# cpuinterface.net
KiCad netlist of a schematic drawn in Altium Designer
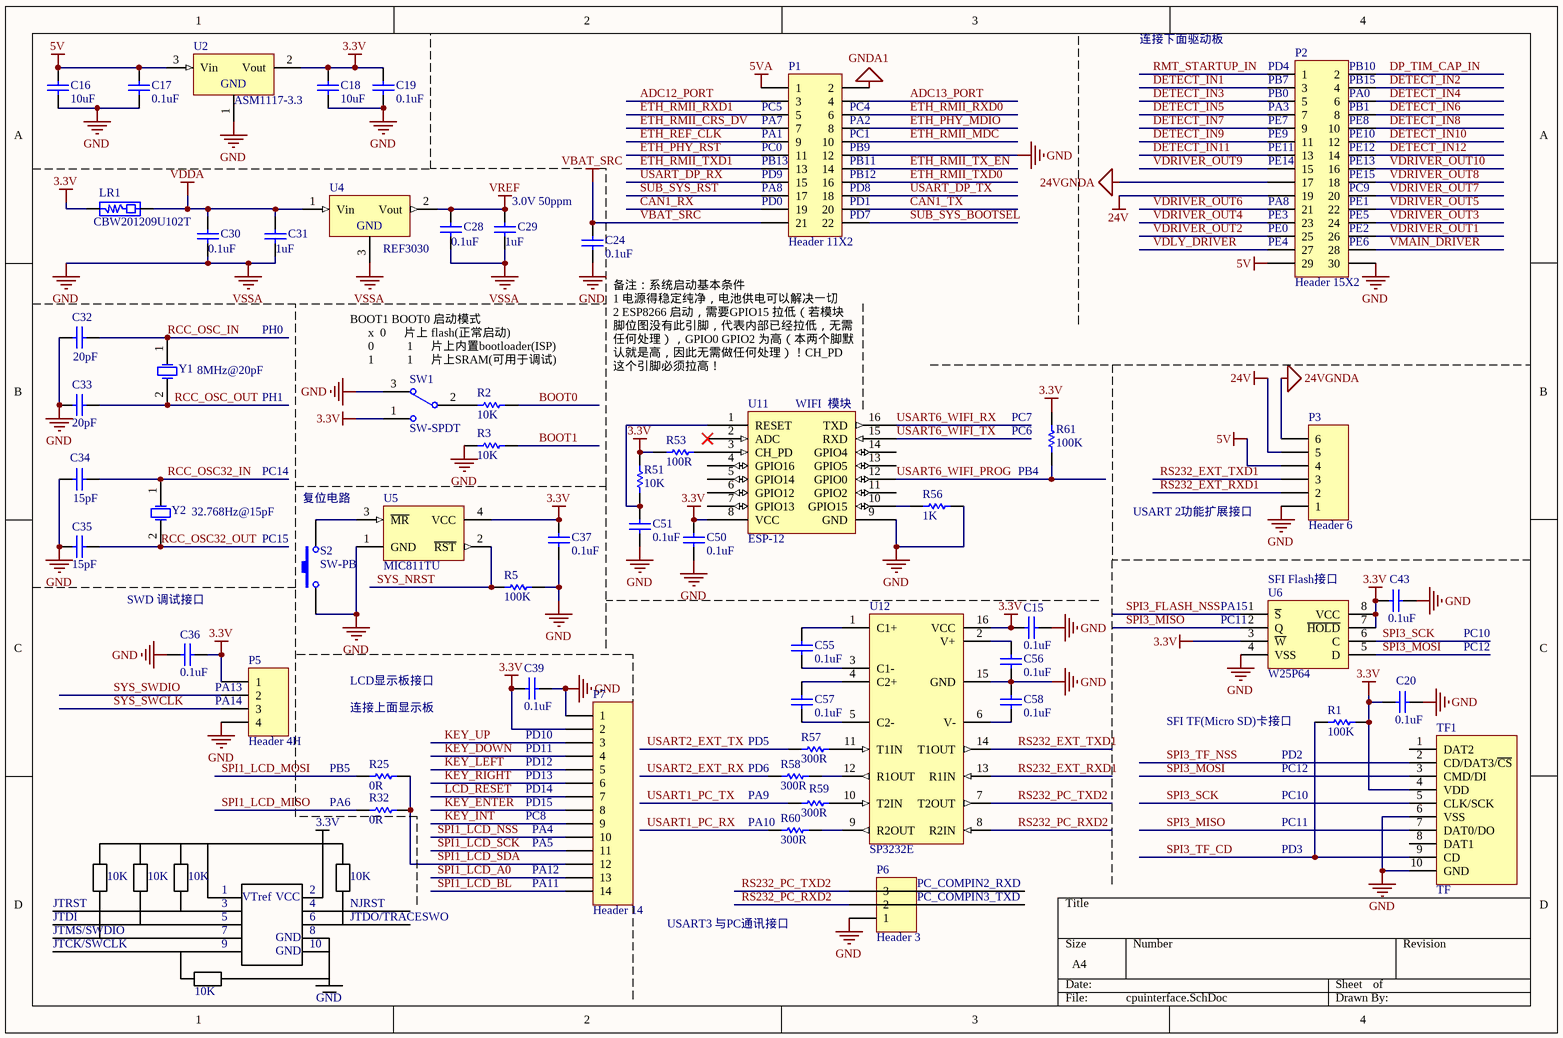
[diagram p0: cpuinterface.SchDoc]

(export (version "E")
  (design (tool "Eeschema 10.0.6"))
  (components
    (comp (ref "C15")
      (value "0.1uF")
      (footprint "CAPC2012M")
      (description "Capacitor")
      (fields (field (name "PUBLISHER") "Altium Limited"))
      (libsource (lib "Miscellaneous Devices") (part "Cap"))
    )
    (comp (ref "C16")
      (value "10uF")
      (footprint "CAPC2012M")
      (description "Capacitor")
      (fields (field (name "PUBLISHER") "Altium Limited"))
      (libsource (lib "Miscellaneous Devices") (part "Cap"))
    )
    (comp (ref "C17")
      (value "0.1uF")
      (footprint "CAPC2012M")
      (description "Capacitor")
      (fields (field (name "PUBLISHER") "Altium Limited"))
      (libsource (lib "Miscellaneous Devices") (part "Cap"))
    )
    (comp (ref "C18")
      (value "10uF")
      (footprint "CAPC2012M")
      (description "Capacitor")
      (fields (field (name "PUBLISHER") "Altium Limited"))
      (libsource (lib "Miscellaneous Devices") (part "Cap"))
    )
    (comp (ref "C19")
      (value "0.1uF")
      (footprint "CAPC2012M")
      (description "Capacitor")
      (fields (field (name "PUBLISHER") "Altium Limited"))
      (libsource (lib "Miscellaneous Devices") (part "Cap"))
    )
    (comp (ref "C20")
      (value "0.1uF")
      (footprint "CAPC2012M")
      (description "Capacitor")
      (fields (field (name "PUBLISHER") "Altium Limited"))
      (libsource (lib "Miscellaneous Devices") (part "Cap"))
    )
    (comp (ref "C24")
      (value "0.1uF")
      (footprint "CAPC2012M")
      (description "Capacitor")
      (fields (field (name "PUBLISHER") "Altium Limited"))
      (libsource (lib "Miscellaneous Devices") (part "Cap"))
    )
    (comp (ref "C28")
      (value "0.1uF")
      (footprint "CAPC2012M")
      (description "Capacitor")
      (fields (field (name "PUBLISHER") "Altium Limited"))
      (libsource (lib "Miscellaneous Devices") (part "Cap"))
    )
    (comp (ref "C29")
      (value "1uF")
      (footprint "CAPC2012M")
      (description "Capacitor")
      (fields (field (name "PUBLISHER") "Altium Limited"))
      (libsource (lib "Miscellaneous Devices") (part "Cap"))
    )
    (comp (ref "C30")
      (value "0.1uF")
      (footprint "CAPC2012M")
      (description "Capacitor")
      (fields (field (name "PUBLISHER") "Altium Limited"))
      (libsource (lib "Miscellaneous Devices") (part "Cap"))
    )
    (comp (ref "C31")
      (value "1uF")
      (footprint "CAPC2012M")
      (description "Capacitor")
      (fields (field (name "PUBLISHER") "Altium Limited"))
      (libsource (lib "Miscellaneous Devices") (part "Cap"))
    )
    (comp (ref "C32")
      (value "20pF")
      (footprint "CAPC2012M")
      (description "Capacitor")
      (fields (field (name "PUBLISHER") "Altium Limited"))
      (libsource (lib "Miscellaneous Devices") (part "Cap"))
    )
    (comp (ref "C33")
      (value "20pF")
      (footprint "CAPC2012M")
      (description "Capacitor")
      (fields (field (name "PUBLISHER") "Altium Limited"))
      (libsource (lib "Miscellaneous Devices") (part "Cap"))
    )
    (comp (ref "C34")
      (value "15pF")
      (footprint "CAPC2012M")
      (description "Capacitor")
      (fields (field (name "PUBLISHER") "Altium Limited"))
      (libsource (lib "Miscellaneous Devices") (part "Cap"))
    )
    (comp (ref "C35")
      (value "15pF")
      (footprint "CAPC2012M")
      (description "Capacitor")
      (fields (field (name "PUBLISHER") "Altium Limited"))
      (libsource (lib "Miscellaneous Devices") (part "Cap"))
    )
    (comp (ref "C36")
      (value "0.1uF")
      (footprint "CAPC2012M")
      (description "Capacitor")
      (fields (field (name "PUBLISHER") "Altium Limited"))
      (libsource (lib "Miscellaneous Devices") (part "Cap"))
    )
    (comp (ref "C37")
      (value "0.1uF")
      (footprint "CAPC2012M")
      (description "Capacitor")
      (fields (field (name "PUBLISHER") "Altium Limited"))
      (libsource (lib "Miscellaneous Devices") (part "Cap"))
    )
    (comp (ref "C39")
      (value "0.1uF")
      (footprint "CAPC2012M")
      (description "Capacitor")
      (fields (field (name "PUBLISHER") "Altium Limited"))
      (libsource (lib "Miscellaneous Devices") (part "Cap"))
    )
    (comp (ref "C43")
      (value "0.1uF")
      (footprint "CAPC2012M")
      (description "Capacitor")
      (fields (field (name "PUBLISHER") "Altium Limited"))
      (libsource (lib "Miscellaneous Devices") (part "Cap"))
    )
    (comp (ref "C50")
      (value "0.1uF")
      (footprint "CAPC2012M")
      (description "Capacitor")
      (fields (field (name "PUBLISHER") "Altium Limited"))
      (libsource (lib "Miscellaneous Devices") (part "Cap"))
    )
    (comp (ref "C51")
      (value "0.1uF")
      (footprint "CAPC2012M")
      (description "Capacitor")
      (fields (field (name "PUBLISHER") "Altium Limited"))
      (libsource (lib "Miscellaneous Devices") (part "Cap"))
    )
    (comp (ref "C55")
      (value "0.1uF")
      (footprint "CAPC2012M")
      (description "Capacitor")
      (fields (field (name "PUBLISHER") "Altium Limited"))
      (libsource (lib "Miscellaneous Devices") (part "Cap"))
    )
    (comp (ref "C56")
      (value "0.1uF")
      (footprint "CAPC2012M")
      (description "Capacitor")
      (fields (field (name "PUBLISHER") "Altium Limited"))
      (libsource (lib "Miscellaneous Devices") (part "Cap"))
    )
    (comp (ref "C57")
      (value "0.1uF")
      (footprint "CAPC2012M")
      (description "Capacitor")
      (fields (field (name "PUBLISHER") "Altium Limited"))
      (libsource (lib "Miscellaneous Devices") (part "Cap"))
    )
    (comp (ref "C58")
      (value "0.1uF")
      (footprint "CAPC2012M")
      (description "Capacitor")
      (fields (field (name "PUBLISHER") "Altium Limited"))
      (libsource (lib "Miscellaneous Devices") (part "Cap"))
    )
    (comp (ref "LR1")
      (value "CBW201209U102T")
      (footprint "INDC2012M")
      (description "EMI FILTERS,DC Resistance max.0.05~1.5 ohms,10 ~ 1000 ohms at 100MHz  Frequency")
      (libsource (lib "UserLib") (part "BLM10/11/21/31/41"))
    )
    (comp (ref "P1")
      (value "Header 11X2")
      (footprint "HDR2X11")
      (description "Header, 11-Pin, Dual row")
      (fields (field (name "PUBLISHER") "Altium Limited"))
      (libsource (lib "UserSchCon") (part "Header 11X2"))
    )
    (comp (ref "P2")
      (value "Header 15X2")
      (footprint "HDR2X15")
      (description "Header, 15-Pin, Dual row")
      (fields (field (name "PUBLISHER") "Altium Limited"))
      (libsource (lib "UserSchCon") (part "Header 15X2"))
    )
    (comp (ref "P3")
      (value "Header 6")
      (footprint "HDR1x6-2.0")
      (description "Header, 6-Pin")
      (fields (field (name "PUBLISHER") "Altium Limited"))
      (libsource (lib "UserSchCon") (part "Header 6"))
    )
    (comp (ref "P5")
      (value "Header 4H")
      (footprint "HDR1X4H-2.0")
      (description "Header, 4-Pin, Right Angle")
      (fields (field (name "PUBLISHER") "Altium Limited"))
      (libsource (lib "UserSchCon") (part "Header 4H"))
    )
    (comp (ref "P6")
      (value "Header 3")
      (footprint "HDR1x3-2.0")
      (description "Header, 3-Pin")
      (fields (field (name "PUBLISHER") "Altium Limited"))
      (libsource (lib "UserSchCon") (part "Header 3"))
    )
    (comp (ref "P7")
      (value "Header 14")
      (footprint "FPC0.5-14P-A")
      (description "Header, 14-Pin")
      (fields (field (name "PUBLISHER") "Altium Limited"))
      (libsource (lib "UserSchCon") (part "Header 14"))
    )
    (comp (ref "R1")
      (value "100K")
      (footprint "RESC2012M")
      (description "Resistor")
      (fields (field (name "PUBLISHER") "Altium Limited"))
      (libsource (lib "Miscellaneous Devices") (part "Res1"))
    )
    (comp (ref "R2")
      (value "10K")
      (footprint "RESC2012M")
      (description "Resistor")
      (fields (field (name "PUBLISHER") "Altium Limited"))
      (libsource (lib "Miscellaneous Devices") (part "Res1"))
    )
    (comp (ref "R3")
      (value "10K")
      (footprint "RESC2012M")
      (description "Resistor")
      (fields (field (name "PUBLISHER") "Altium Limited"))
      (libsource (lib "Miscellaneous Devices") (part "Res1"))
    )
    (comp (ref "R5")
      (value "100K")
      (footprint "RESC2012M")
      (description "Resistor")
      (fields (field (name "PUBLISHER") "Altium Limited"))
      (libsource (lib "Miscellaneous Devices") (part "Res1"))
    )
    (comp (ref "R25")
      (value "0R")
      (footprint "RESC2012M")
      (description "Resistor")
      (fields (field (name "PUBLISHER") "Altium Limited"))
      (libsource (lib "Miscellaneous Devices") (part "Res1"))
    )
    (comp (ref "R32")
      (value "0R")
      (footprint "RESC2012M")
      (description "Resistor")
      (fields (field (name "PUBLISHER") "Altium Limited"))
      (libsource (lib "Miscellaneous Devices") (part "Res1"))
    )
    (comp (ref "R51")
      (value "10K")
      (footprint "RESC2012M")
      (description "Resistor")
      (fields (field (name "PUBLISHER") "Altium Limited"))
      (libsource (lib "Miscellaneous Devices") (part "Res1"))
    )
    (comp (ref "R53")
      (value "100R")
      (footprint "RESC2012M")
      (description "Resistor")
      (fields (field (name "PUBLISHER") "Altium Limited"))
      (libsource (lib "Miscellaneous Devices") (part "Res1"))
    )
    (comp (ref "R56")
      (value "1K")
      (footprint "RESC2012M")
      (description "Resistor")
      (fields (field (name "PUBLISHER") "Altium Limited"))
      (libsource (lib "Miscellaneous Devices") (part "Res1"))
    )
    (comp (ref "R57")
      (value "300R")
      (footprint "RESC2012M")
      (description "Resistor")
      (fields (field (name "PUBLISHER") "Altium Limited"))
      (libsource (lib "Miscellaneous Devices") (part "Res1"))
    )
    (comp (ref "R58")
      (value "300R")
      (footprint "RESC2012M")
      (description "Resistor")
      (fields (field (name "PUBLISHER") "Altium Limited"))
      (libsource (lib "Miscellaneous Devices") (part "Res1"))
    )
    (comp (ref "R59")
      (value "300R")
      (footprint "RESC2012M")
      (description "Resistor")
      (fields (field (name "PUBLISHER") "Altium Limited"))
      (libsource (lib "Miscellaneous Devices") (part "Res1"))
    )
    (comp (ref "R60")
      (value "300R")
      (footprint "RESC2012M")
      (description "Resistor")
      (fields (field (name "PUBLISHER") "Altium Limited"))
      (libsource (lib "Miscellaneous Devices") (part "Res1"))
    )
    (comp (ref "R61")
      (value "100K")
      (footprint "RESC2012M")
      (description "Resistor")
      (fields (field (name "PUBLISHER") "Altium Limited"))
      (libsource (lib "Miscellaneous Devices") (part "Res1"))
    )
    (comp (ref "S2")
      (value "SW-PB")
      (footprint "PBSMT-6x3x3.5R")
      (description "Push Button ,2mm(L)x2mm(W)x10mm(H)")
      (fields (field (name "PUBLISHER") "Altium Limited"))
      (libsource (lib "Miscellaneous Devices") (part "SW-PB"))
    )
    (comp (ref "SW1")
      (value "SW-SPDT")
      (footprint "SW-9x3.5x3.5RS")
      (description "开关")
      (fields (field (name "PUBLISHER") "Altium Limited"))
      (libsource (lib "UserSchDev") (part "SW-SPDT_1"))
    )
    (comp (ref "TF1") (value "TF") (footprint "TF-PUSH") (libsource (lib "UserSchDev") (part "TF")))
    (comp (ref "U2")
      (value "ASM1117-3.3")
      (footprint "SOT-223")
      (description "800mA Low-Dropout Linear Regulator")
      (libsource (lib "UserLib") (part "LM1117T-5.0"))
    )
    (comp (ref "U4")
      (value "REF3030")
      (footprint "SOT23_M")
      (description "1.25V 1.8V 2.048V 2.5V 3.0V 3.3V 4.096V reference voltage")
      (libsource (lib "UserSchDev") (part "REF3330"))
    )
    (comp (ref "U5")
      (value "MIC811TU")
      (footprint "SOT-143_N")
      (description "4-Pin 礟 Voltage Monitors with Manual Reset Input")
      (fields (field (name "PUBLISHER") "Altium Limited"))
      (libsource (lib "Maxim Power Mgt Supervisory Circuit") (part "MAX811-EUS-T"))
    )
    (comp (ref "U6")
      (value "W25P64")
      (footprint "SOIC8_W")
      (description "32 Mbit, Low Voltage, Serial Flash Memory  With 50MHz SPI Bus Interface")
      (libsource (lib "UserSchDev") (part "M25P32"))
    )
    (comp (ref "U11")
      (value "ESP-12")
      (footprint "ESP-12")
      (description "SOC Wifi Mode")
      (libsource (lib "UserSchDev") (part "ESP-12"))
    )
    (comp (ref "U12")
      (value "SP3232E")
      (footprint "NSO16_M")
      (description "+3.0V+5V Powered, Multi-Channel RS-232 Driver/Receiver")
      (fields (field (name "PUBLISHER") "Altium Limited"))
      (libsource (lib "UserSchDev") (part "SP3232E"))
    )
    (comp (ref "Y1")
      (value "8MHz@20pF")
      (footprint "HC-49U")
      (description "Crystal Oscillator")
      (fields (field (name "PUBLISHER") "Altium Limited"))
      (libsource (lib "Miscellaneous Devices") (part "XTAL"))
    )
    (comp (ref "Y2")
      (value "32.768Hz@15pF")
      (footprint "HC-RTC-L")
      (description "Crystal Oscillator")
      (fields (field (name "PUBLISHER") "Altium Limited"))
      (libsource (lib "Miscellaneous Devices") (part "XTAL"))
    )
  )
  (nets
    (net (code "1") (name "/ADC12_PORT") (class "Default")
      (node (ref "P1") (pin "3") (pinfunction "3_3") (pintype "passive"))
    )
    (net (code "2") (name "/ADC13_PORT") (class "Default")
      (node (ref "P1") (pin "4") (pinfunction "4_4") (pintype "passive"))
    )
    (net (code "3") (name "/BOOT0") (class "Default")
      (node (ref "R2") (pin "1") (pinfunction "1_1") (pintype "passive"))
    )
    (net (code "4") (name "/BOOT1") (class "Default")
      (node (ref "R3") (pin "1") (pinfunction "1_1") (pintype "passive"))
    )
    (net (code "5") (name "/CAN1_RX") (class "Default")
      (node (ref "P1") (pin "19") (pinfunction "19_19") (pintype "passive"))
    )
    (net (code "6") (name "/CAN1_TX") (class "Default")
      (node (ref "P1") (pin "20") (pinfunction "20_20") (pintype "passive"))
    )
    (net (code "7") (name "/DETECT_IN1") (class "Default")
      (node (ref "P2") (pin "3") (pinfunction "3_3") (pintype "passive"))
    )
    (net (code "8") (name "/DETECT_IN2") (class "Default")
      (node (ref "P2") (pin "4") (pinfunction "4_4") (pintype "passive"))
    )
    (net (code "9") (name "/DETECT_IN3") (class "Default")
      (node (ref "P2") (pin "5") (pinfunction "5_5") (pintype "passive"))
    )
    (net (code "10") (name "/DETECT_IN4") (class "Default")
      (node (ref "P2") (pin "6") (pinfunction "6_6") (pintype "passive"))
    )
    (net (code "11") (name "/DETECT_IN5") (class "Default")
      (node (ref "P2") (pin "7") (pinfunction "7_7") (pintype "passive"))
    )
    (net (code "12") (name "/DETECT_IN6") (class "Default")
      (node (ref "P2") (pin "8") (pinfunction "8_8") (pintype "passive"))
    )
    (net (code "13") (name "/DETECT_IN7") (class "Default")
      (node (ref "P2") (pin "9") (pinfunction "9_9") (pintype "passive"))
    )
    (net (code "14") (name "/DETECT_IN8") (class "Default")
      (node (ref "P2") (pin "10") (pinfunction "10_10") (pintype "passive"))
    )
    (net (code "15") (name "/DETECT_IN9") (class "Default")
      (node (ref "P2") (pin "11") (pinfunction "11_11") (pintype "passive"))
    )
    (net (code "16") (name "/DETECT_IN10") (class "Default")
      (node (ref "P2") (pin "12") (pinfunction "12_12") (pintype "passive"))
    )
    (net (code "17") (name "/DETECT_IN11") (class "Default")
      (node (ref "P2") (pin "13") (pinfunction "13_13") (pintype "passive"))
    )
    (net (code "18") (name "/DETECT_IN12") (class "Default")
      (node (ref "P2") (pin "14") (pinfunction "14_14") (pintype "passive"))
    )
    (net (code "19") (name "/DP_TIM_CAP_IN") (class "Default")
      (node (ref "P2") (pin "2") (pinfunction "2_2") (pintype "passive"))
    )
    (net (code "20") (name "/ETH_PHY_MDIO") (class "Default")
      (node (ref "P1") (pin "8") (pinfunction "8_8") (pintype "passive"))
    )
    (net (code "21") (name "/ETH_PHY_RST") (class "Default")
      (node (ref "P1") (pin "11") (pinfunction "11_11") (pintype "passive"))
    )
    (net (code "22") (name "/ETH_REF_CLK") (class "Default")
      (node (ref "P1") (pin "9") (pinfunction "9_9") (pintype "passive"))
    )
    (net (code "23") (name "/ETH_RMII_CRS_DV") (class "Default")
      (node (ref "P1") (pin "7") (pinfunction "7_7") (pintype "passive"))
    )
    (net (code "24") (name "/ETH_RMII_MDC") (class "Default")
      (node (ref "P1") (pin "10") (pinfunction "10_10") (pintype "passive"))
    )
    (net (code "25") (name "/ETH_RMII_RXD0") (class "Default")
      (node (ref "P1") (pin "6") (pinfunction "6_6") (pintype "passive"))
    )
    (net (code "26") (name "/ETH_RMII_RXD1") (class "Default")
      (node (ref "P1") (pin "5") (pinfunction "5_5") (pintype "passive"))
    )
    (net (code "27") (name "/ETH_RMII_TXD0") (class "Default")
      (node (ref "P1") (pin "16") (pinfunction "16_16") (pintype "passive"))
    )
    (net (code "28") (name "/ETH_RMII_TXD1") (class "Default")
      (node (ref "P1") (pin "13") (pinfunction "13_13") (pintype "passive"))
    )
    (net (code "29") (name "/ETH_RMII_TX_EN") (class "Default")
      (node (ref "P1") (pin "14") (pinfunction "14_14") (pintype "passive"))
    )
    (net (code "30") (name "/KEY_DOWN") (class "Default")
      (node (ref "P7") (pin "4") (pinfunction "4_4") (pintype "passive"))
    )
    (net (code "31") (name "/KEY_ENTER") (class "Default")
      (node (ref "P7") (pin "8") (pinfunction "8_8") (pintype "passive"))
    )
    (net (code "32") (name "/KEY_INT") (class "Default")
      (node (ref "P7") (pin "9") (pinfunction "9_9") (pintype "passive"))
    )
    (net (code "33") (name "/KEY_LEFT") (class "Default")
      (node (ref "P7") (pin "5") (pinfunction "5_5") (pintype "passive"))
    )
    (net (code "34") (name "/KEY_RIGHT") (class "Default")
      (node (ref "P7") (pin "6") (pinfunction "6_6") (pintype "passive"))
    )
    (net (code "35") (name "/KEY_UP") (class "Default")
      (node (ref "P7") (pin "3") (pinfunction "3_3") (pintype "passive"))
    )
    (net (code "36") (name "/LCD_RESET") (class "Default")
      (node (ref "P7") (pin "7") (pinfunction "7_7") (pintype "passive"))
    )
    (net (code "37") (name "/RCC_OSC32_IN") (class "Default")
      (node (ref "C34") (pin "1") (pinfunction "1_1") (pintype "passive"))
      (node (ref "Y2") (pin "1") (pinfunction "OSC1_1") (pintype "passive"))
    )
    (net (code "38") (name "/RCC_OSC32_OUT") (class "Default")
      (node (ref "C35") (pin "1") (pinfunction "1_1") (pintype "passive"))
      (node (ref "Y2") (pin "2") (pinfunction "OSC2_2") (pintype "passive"))
    )
    (net (code "39") (name "/RCC_OSC_IN") (class "Default")
      (node (ref "C32") (pin "1") (pinfunction "1_1") (pintype "passive"))
      (node (ref "Y1") (pin "1") (pinfunction "OSC1_1") (pintype "passive"))
    )
    (net (code "40") (name "/RCC_OSC_OUT") (class "Default")
      (node (ref "C33") (pin "1") (pinfunction "1_1") (pintype "passive"))
      (node (ref "Y1") (pin "2") (pinfunction "OSC2_2") (pintype "passive"))
    )
    (net (code "41") (name "/RMT_STARTUP_IN") (class "Default")
      (node (ref "P2") (pin "1") (pinfunction "1_1") (pintype "passive"))
    )
    (net (code "42") (name "/RS232_EXT_RXD1") (class "Default")
      (node (ref "P3") (pin "2") (pinfunction "2_2") (pintype "passive"))
      (node (ref "U12") (pin "13") (pinfunction "R1IN_13") (pintype "input"))
    )
    (net (code "43") (name "/RS232_EXT_TXD1") (class "Default")
      (node (ref "P3") (pin "3") (pinfunction "3_3") (pintype "passive"))
      (node (ref "U12") (pin "14") (pinfunction "T1OUT_14") (pintype "output"))
    )
    (net (code "44") (name "/RS232_PC_RXD2") (class "Default")
      (node (ref "P6") (pin "2") (pinfunction "2_2") (pintype "passive"))
      (node (ref "U12") (pin "8") (pinfunction "R2IN_8") (pintype "input"))
    )
    (net (code "45") (name "/RS232_PC_TXD2") (class "Default")
      (node (ref "P6") (pin "3") (pinfunction "3_3") (pintype "passive"))
      (node (ref "U12") (pin "7") (pinfunction "T2OUT_7") (pintype "output"))
    )
    (net (code "46") (name "/SPI1_LCD_A0") (class "Default")
      (node (ref "P7") (pin "13") (pinfunction "13_13") (pintype "passive"))
    )
    (net (code "47") (name "/SPI1_LCD_BL") (class "Default")
      (node (ref "P7") (pin "14") (pinfunction "14_14") (pintype "passive"))
    )
    (net (code "48") (name "/SPI1_LCD_MISO") (class "Default")
      (node (ref "R32") (pin "1") (pinfunction "1_1") (pintype "passive"))
    )
    (net (code "49") (name "/SPI1_LCD_MOSI") (class "Default")
      (node (ref "R25") (pin "1") (pinfunction "1_1") (pintype "passive"))
    )
    (net (code "50") (name "/SPI1_LCD_NSS") (class "Default")
      (node (ref "P7") (pin "10") (pinfunction "10_10") (pintype "passive"))
    )
    (net (code "51") (name "/SPI1_LCD_SCK") (class "Default")
      (node (ref "P7") (pin "11") (pinfunction "11_11") (pintype "passive"))
    )
    (net (code "52") (name "/SPI1_LCD_SDA") (class "Default")
      (node (ref "P7") (pin "12") (pinfunction "12_12") (pintype "passive"))
      (node (ref "R25") (pin "2") (pinfunction "2_2") (pintype "passive"))
      (node (ref "R32") (pin "2") (pinfunction "2_2") (pintype "passive"))
    )
    (net (code "53") (name "/SPI3_FLASH_NSS") (class "Default")
      (node (ref "U6") (pin "1") (pinfunction "~{S}_1") (pintype "passive"))
    )
    (net (code "54") (name "/SPI3_MISO") (class "Default")
      (node (ref "TF1") (pin "7") (pinfunction "DAT0/DO_7") (pintype "passive"))
      (node (ref "U6") (pin "2") (pinfunction "Q_2") (pintype "passive"))
    )
    (net (code "55") (name "/SPI3_MOSI") (class "Default")
      (node (ref "TF1") (pin "3") (pinfunction "CMD/DI_3") (pintype "passive"))
      (node (ref "U6") (pin "5") (pinfunction "D_5") (pintype "passive"))
    )
    (net (code "56") (name "/SPI3_SCK") (class "Default")
      (node (ref "TF1") (pin "5") (pinfunction "CLK/SCK_5") (pintype "passive"))
      (node (ref "U6") (pin "6") (pinfunction "C_6") (pintype "passive"))
    )
    (net (code "57") (name "/SPI3_TF_CD") (class "Default")
      (node (ref "R1") (pin "1") (pinfunction "1_1") (pintype "passive"))
      (node (ref "TF1") (pin "9") (pinfunction "CD_9") (pintype "power_in"))
    )
    (net (code "58") (name "/SPI3_TF_NSS") (class "Default")
      (node (ref "TF1") (pin "2") (pinfunction "CD/DAT3/~{CS}_2") (pintype "passive"))
    )
    (net (code "59") (name "/SUB_SYS_BOOTSEL") (class "Default")
      (node (ref "P1") (pin "22") (pinfunction "22_22") (pintype "passive"))
    )
    (net (code "60") (name "/SUB_SYS_RST") (class "Default")
      (node (ref "P1") (pin "17") (pinfunction "17_17") (pintype "passive"))
    )
    (net (code "61") (name "/SYS_NRST") (class "Default")
      (node (ref "R5") (pin "1") (pinfunction "1_1") (pintype "passive"))
      (node (ref "U5") (pin "2") (pinfunction "~{RST}_2") (pintype "output"))
    )
    (net (code "62") (name "/SYS_SWCLK") (class "Default")
      (node (ref "P5") (pin "3") (pinfunction "3_3") (pintype "passive"))
    )
    (net (code "63") (name "/SYS_SWDIO") (class "Default")
      (node (ref "P5") (pin "2") (pinfunction "2_2") (pintype "passive"))
    )
    (net (code "64") (name "/USART1_PC_RX") (class "Default")
      (node (ref "R60") (pin "2") (pinfunction "2_2") (pintype "passive"))
    )
    (net (code "65") (name "/USART1_PC_TX") (class "Default")
      (node (ref "R59") (pin "1") (pinfunction "1_1") (pintype "passive"))
    )
    (net (code "66") (name "/USART2_EXT_RX") (class "Default")
      (node (ref "R58") (pin "1") (pinfunction "1_1") (pintype "passive"))
    )
    (net (code "67") (name "/USART2_EXT_TX") (class "Default")
      (node (ref "R57") (pin "1") (pinfunction "1_1") (pintype "passive"))
    )
    (net (code "68") (name "/USART6_WIFI_PROG") (class "Default")
      (node (ref "R61") (pin "2") (pinfunction "2_2") (pintype "passive"))
      (node (ref "U11") (pin "12") (pinfunction "GPIO0_12") (pintype "bidirectional"))
    )
    (net (code "69") (name "/USART6_WIFI_RX") (class "Default")
      (node (ref "U11") (pin "16") (pinfunction "TXD_16") (pintype "output"))
    )
    (net (code "70") (name "/USART6_WIFI_TX") (class "Default")
      (node (ref "U11") (pin "15") (pinfunction "RXD_15") (pintype "input"))
    )
    (net (code "71") (name "/USART_DP_RX") (class "Default")
      (node (ref "P1") (pin "15") (pinfunction "15_15") (pintype "passive"))
    )
    (net (code "72") (name "/USART_DP_TX") (class "Default")
      (node (ref "P1") (pin "18") (pinfunction "18_18") (pintype "passive"))
    )
    (net (code "73") (name "/VDLY_DRIVER") (class "Default")
      (node (ref "P2") (pin "27") (pinfunction "27_27") (pintype "passive"))
    )
    (net (code "74") (name "/VDRIVER_OUT1") (class "Default")
      (node (ref "P2") (pin "26") (pinfunction "26_26") (pintype "passive"))
    )
    (net (code "75") (name "/VDRIVER_OUT2") (class "Default")
      (node (ref "P2") (pin "25") (pinfunction "25_25") (pintype "passive"))
    )
    (net (code "76") (name "/VDRIVER_OUT3") (class "Default")
      (node (ref "P2") (pin "24") (pinfunction "24_24") (pintype "passive"))
    )
    (net (code "77") (name "/VDRIVER_OUT4") (class "Default")
      (node (ref "P2") (pin "23") (pinfunction "23_23") (pintype "passive"))
    )
    (net (code "78") (name "/VDRIVER_OUT5") (class "Default")
      (node (ref "P2") (pin "22") (pinfunction "22_22") (pintype "passive"))
    )
    (net (code "79") (name "/VDRIVER_OUT6") (class "Default")
      (node (ref "P2") (pin "21") (pinfunction "21_21") (pintype "passive"))
    )
    (net (code "80") (name "/VDRIVER_OUT7") (class "Default")
      (node (ref "P2") (pin "20") (pinfunction "20_20") (pintype "passive"))
    )
    (net (code "81") (name "/VDRIVER_OUT8") (class "Default")
      (node (ref "P2") (pin "18") (pinfunction "18_18") (pintype "passive"))
    )
    (net (code "82") (name "/VDRIVER_OUT9") (class "Default")
      (node (ref "P2") (pin "15") (pinfunction "15_15") (pintype "passive"))
    )
    (net (code "83") (name "/VDRIVER_OUT10") (class "Default")
      (node (ref "P2") (pin "16") (pinfunction "16_16") (pintype "passive"))
    )
    (net (code "84") (name "/VMAIN_DRIVER") (class "Default")
      (node (ref "P2") (pin "28") (pinfunction "28_28") (pintype "passive"))
    )
    (net (code "85") (name "3.3V") (class "Default")
      (node (ref "C15") (pin "2") (pinfunction "2_2") (pintype "passive"))
      (node (ref "C18") (pin "2") (pinfunction "2_2") (pintype "passive"))
      (node (ref "C19") (pin "2") (pinfunction "2_2") (pintype "passive"))
      (node (ref "C20") (pin "1") (pinfunction "1_1") (pintype "passive"))
      (node (ref "C36") (pin "2") (pinfunction "2_2") (pintype "passive"))
      (node (ref "C37") (pin "2") (pinfunction "2_2") (pintype "passive"))
      (node (ref "C39") (pin "2") (pinfunction "2_2") (pintype "passive"))
      (node (ref "C43") (pin "1") (pinfunction "1_1") (pintype "passive"))
      (node (ref "C50") (pin "1") (pinfunction "1_1") (pintype "passive"))
      (node (ref "LR1") (pin "1") (pinfunction "1_1") (pintype "passive"))
      (node (ref "P5") (pin "1") (pinfunction "1_1") (pintype "passive"))
      (node (ref "P7") (pin "2") (pinfunction "2_2") (pintype "passive"))
      (node (ref "R1") (pin "2") (pinfunction "2_2") (pintype "passive"))
      (node (ref "R51") (pin "1") (pinfunction "1_1") (pintype "passive"))
      (node (ref "R53") (pin "1") (pinfunction "1_1") (pintype "passive"))
      (node (ref "R61") (pin "1") (pinfunction "1_1") (pintype "passive"))
      (node (ref "SW1") (pin "1") (pinfunction "1_1") (pintype "passive"))
      (node (ref "TF1") (pin "4") (pinfunction "VDD_4") (pintype "passive"))
      (node (ref "U11") (pin "8") (pinfunction "VCC_8") (pintype "power_in"))
      (node (ref "U12") (pin "16") (pinfunction "VCC_16") (pintype "power_in"))
      (node (ref "U2") (pin "2") (pinfunction "Vout_2") (pintype "power_in"))
      (node (ref "U5") (pin "4") (pinfunction "VCC_4") (pintype "power_in"))
      (node (ref "U6") (pin "3") (pinfunction "~{W}_3") (pintype "passive"))
      (node (ref "U6") (pin "7") (pinfunction "~{HOLD}_7") (pintype "passive"))
      (node (ref "U6") (pin "8") (pinfunction "VCC_8") (pintype "power_in"))
    )
    (net (code "86") (name "5V") (class "Default")
      (node (ref "C16") (pin "2") (pinfunction "2_2") (pintype "passive"))
      (node (ref "C17") (pin "2") (pinfunction "2_2") (pintype "passive"))
      (node (ref "P2") (pin "29") (pinfunction "29_29") (pintype "passive"))
      (node (ref "P3") (pin "4") (pinfunction "4_4") (pintype "passive"))
      (node (ref "U2") (pin "3") (pinfunction "Vin_3") (pintype "input"))
    )
    (net (code "87") (name "5VA") (class "Default")
      (node (ref "P1") (pin "1") (pinfunction "1_1") (pintype "passive"))
    )
    (net (code "88") (name "24V") (class "Default")
      (node (ref "P2") (pin "19") (pinfunction "19_19") (pintype "passive"))
      (node (ref "P3") (pin "5") (pinfunction "5_5") (pintype "passive"))
    )
    (net (code "89") (name "24VGNDA") (class "Default")
      (node (ref "P2") (pin "17") (pinfunction "17_17") (pintype "passive"))
      (node (ref "P3") (pin "6") (pinfunction "6_6") (pintype "passive"))
    )
    (net (code "90") (name "GND") (class "Default")
      (node (ref "C15") (pin "1") (pinfunction "1_1") (pintype "passive"))
      (node (ref "C16") (pin "1") (pinfunction "1_1") (pintype "passive"))
      (node (ref "C17") (pin "1") (pinfunction "1_1") (pintype "passive"))
      (node (ref "C18") (pin "1") (pinfunction "1_1") (pintype "passive"))
      (node (ref "C19") (pin "1") (pinfunction "1_1") (pintype "passive"))
      (node (ref "C20") (pin "2") (pinfunction "2_2") (pintype "passive"))
      (node (ref "C24") (pin "2") (pinfunction "2_2") (pintype "passive"))
      (node (ref "C28") (pin "1") (pinfunction "1_1") (pintype "passive"))
      (node (ref "C29") (pin "1") (pinfunction "1_1") (pintype "passive"))
      (node (ref "C30") (pin "1") (pinfunction "1_1") (pintype "passive"))
      (node (ref "C31") (pin "1") (pinfunction "1_1") (pintype "passive"))
      (node (ref "C32") (pin "2") (pinfunction "2_2") (pintype "passive"))
      (node (ref "C33") (pin "2") (pinfunction "2_2") (pintype "passive"))
      (node (ref "C34") (pin "2") (pinfunction "2_2") (pintype "passive"))
      (node (ref "C35") (pin "2") (pinfunction "2_2") (pintype "passive"))
      (node (ref "C36") (pin "1") (pinfunction "1_1") (pintype "passive"))
      (node (ref "C37") (pin "1") (pinfunction "1_1") (pintype "passive"))
      (node (ref "C39") (pin "1") (pinfunction "1_1") (pintype "passive"))
      (node (ref "C43") (pin "2") (pinfunction "2_2") (pintype "passive"))
      (node (ref "C50") (pin "2") (pinfunction "2_2") (pintype "passive"))
      (node (ref "C51") (pin "2") (pinfunction "2_2") (pintype "passive"))
      (node (ref "C56") (pin "1") (pinfunction "1_1") (pintype "passive"))
      (node (ref "C58") (pin "2") (pinfunction "2_2") (pintype "passive"))
      (node (ref "P1") (pin "12") (pinfunction "12_12") (pintype "passive"))
      (node (ref "P2") (pin "30") (pinfunction "30_30") (pintype "passive"))
      (node (ref "P3") (pin "1") (pinfunction "1_1") (pintype "passive"))
      (node (ref "P5") (pin "4") (pinfunction "4_4") (pintype "passive"))
      (node (ref "P6") (pin "1") (pinfunction "1_1") (pintype "passive"))
      (node (ref "P7") (pin "1") (pinfunction "1_1") (pintype "passive"))
      (node (ref "R3") (pin "2") (pinfunction "2_2") (pintype "passive"))
      (node (ref "R5") (pin "2") (pinfunction "2_2") (pintype "passive"))
      (node (ref "R56") (pin "1") (pinfunction "1_1") (pintype "passive"))
      (node (ref "S2") (pin "1") (pinfunction "1_1") (pintype "passive"))
      (node (ref "SW1") (pin "3") (pinfunction "3_3") (pintype "passive"))
      (node (ref "TF1") (pin "10") (pinfunction "GND_10") (pintype "power_in"))
      (node (ref "TF1") (pin "6") (pinfunction "VSS_6") (pintype "power_in"))
      (node (ref "U11") (pin "9") (pinfunction "GND_9") (pintype "power_in"))
      (node (ref "U12") (pin "15") (pinfunction "GND_15") (pintype "power_in"))
      (node (ref "U2") (pin "1") (pinfunction "GND_1") (pintype "passive"))
      (node (ref "U4") (pin "3") (pinfunction "GND_3") (pintype "passive"))
      (node (ref "U5") (pin "1") (pinfunction "GND_1") (pintype "power_in"))
      (node (ref "U6") (pin "4") (pinfunction "VSS_4") (pintype "power_in"))
    )
    (net (code "91") (name "GNDA1") (class "Default")
      (node (ref "P1") (pin "2") (pinfunction "2_2") (pintype "passive"))
    )
    (net (code "92") (name "Net-(R2-Pad2)") (class "Default")
      (node (ref "R2") (pin "2") (pinfunction "2_2") (pintype "passive"))
      (node (ref "SW1") (pin "2") (pinfunction "2_2") (pintype "passive"))
    )
    (net (code "93") (name "Net-(U5-~{MR})") (class "Default")
      (node (ref "S2") (pin "2") (pinfunction "2_2") (pintype "passive"))
      (node (ref "U5") (pin "3") (pinfunction "~{MR}_3") (pintype "input"))
    )
    (net (code "94") (name "Net-(U11-CH_PD)") (class "Default")
      (node (ref "R53") (pin "2") (pinfunction "2_2") (pintype "passive"))
      (node (ref "U11") (pin "3") (pinfunction "CH_PD_3") (pintype "input"))
    )
    (net (code "95") (name "Net-(U11-GPIO15)") (class "Default")
      (node (ref "R56") (pin "2") (pinfunction "2_2") (pintype "passive"))
      (node (ref "U11") (pin "10") (pinfunction "GPIO15_10") (pintype "bidirectional"))
    )
    (net (code "96") (name "Net-(U11-RESET)") (class "Default")
      (node (ref "C51") (pin "1") (pinfunction "1_1") (pintype "passive"))
      (node (ref "R51") (pin "2") (pinfunction "2_2") (pintype "passive"))
      (node (ref "U11") (pin "1") (pinfunction "RESET_1") (pintype "passive"))
    )
    (net (code "97") (name "Net-(U12-C1+)") (class "Default")
      (node (ref "C55") (pin "1") (pinfunction "1_1") (pintype "passive"))
      (node (ref "U12") (pin "1") (pinfunction "C1+_1") (pintype "passive"))
    )
    (net (code "98") (name "Net-(U12-C1-)") (class "Default")
      (node (ref "C55") (pin "2") (pinfunction "2_2") (pintype "passive"))
      (node (ref "U12") (pin "3") (pinfunction "C1-_3") (pintype "passive"))
    )
    (net (code "99") (name "Net-(U12-C2+)") (class "Default")
      (node (ref "C57") (pin "2") (pinfunction "2_2") (pintype "passive"))
      (node (ref "U12") (pin "4") (pinfunction "C2+_4") (pintype "passive"))
    )
    (net (code "100") (name "Net-(U12-C2-)") (class "Default")
      (node (ref "C57") (pin "1") (pinfunction "1_1") (pintype "passive"))
      (node (ref "U12") (pin "5") (pinfunction "C2-_5") (pintype "passive"))
    )
    (net (code "101") (name "Net-(U12-R1OUT)") (class "Default")
      (node (ref "R58") (pin "2") (pinfunction "2_2") (pintype "passive"))
      (node (ref "U12") (pin "12") (pinfunction "R1OUT_12") (pintype "output"))
    )
    (net (code "102") (name "Net-(U12-R2OUT)") (class "Default")
      (node (ref "R60") (pin "1") (pinfunction "1_1") (pintype "passive"))
      (node (ref "U12") (pin "9") (pinfunction "R2OUT_9") (pintype "output"))
    )
    (net (code "103") (name "Net-(U12-T1IN)") (class "Default")
      (node (ref "R57") (pin "2") (pinfunction "2_2") (pintype "passive"))
      (node (ref "U12") (pin "11") (pinfunction "T1IN_11") (pintype "input"))
    )
    (net (code "104") (name "Net-(U12-T2IN)") (class "Default")
      (node (ref "R59") (pin "2") (pinfunction "2_2") (pintype "passive"))
      (node (ref "U12") (pin "10") (pinfunction "T2IN_10") (pintype "input"))
    )
    (net (code "105") (name "Net-(U12-V+)") (class "Default")
      (node (ref "C56") (pin "2") (pinfunction "2_2") (pintype "passive"))
      (node (ref "U12") (pin "2") (pinfunction "V+_2") (pintype "power_in"))
    )
    (net (code "106") (name "Net-(U12-V-)") (class "Default")
      (node (ref "C58") (pin "1") (pinfunction "1_1") (pintype "passive"))
      (node (ref "U12") (pin "6") (pinfunction "V-_6") (pintype "power_in"))
    )
    (net (code "107") (name "VBAT_SRC") (class "Default")
      (node (ref "C24") (pin "1") (pinfunction "1_1") (pintype "passive"))
      (node (ref "P1") (pin "21") (pinfunction "21_21") (pintype "passive"))
    )
    (net (code "108") (name "VDDA") (class "Default")
      (node (ref "C30") (pin "2") (pinfunction "2_2") (pintype "passive"))
      (node (ref "C31") (pin "2") (pinfunction "2_2") (pintype "passive"))
      (node (ref "LR1") (pin "2") (pinfunction "2_2") (pintype "passive"))
      (node (ref "U4") (pin "1") (pinfunction "Vin_1") (pintype "input"))
    )
    (net (code "109") (name "VREF") (class "Default")
      (node (ref "C28") (pin "2") (pinfunction "2_2") (pintype "passive"))
      (node (ref "C29") (pin "2") (pinfunction "2_2") (pintype "passive"))
      (node (ref "U4") (pin "2") (pinfunction "Vout_2") (pintype "output"))
    )
    (net (code "110") (name "unconnected-(TF1-DAT1-Pad8)") (class "Default")
      (node (ref "TF1") (pin "8") (pinfunction "DAT1_8") (pintype "passive"))
    )
    (net (code "111") (name "unconnected-(TF1-DAT2-Pad1)") (class "Default")
      (node (ref "TF1") (pin "1") (pinfunction "DAT2_1") (pintype "passive"))
    )
    (net (code "112") (name "unconnected-(U11-ADC-Pad2)") (class "Default")
      (node (ref "U11") (pin "2") (pinfunction "ADC_2") (pintype "input+no_connect"))
    )
    (net (code "113") (name "unconnected-(U11-GPIO2-Pad11)") (class "Default")
      (node (ref "U11") (pin "11") (pinfunction "GPIO2_11") (pintype "bidirectional"))
    )
    (net (code "114") (name "unconnected-(U11-GPIO4-Pad14)") (class "Default")
      (node (ref "U11") (pin "14") (pinfunction "GPIO4_14") (pintype "bidirectional"))
    )
    (net (code "115") (name "unconnected-(U11-GPIO5-Pad13)") (class "Default")
      (node (ref "U11") (pin "13") (pinfunction "GPIO5_13") (pintype "bidirectional"))
    )
    (net (code "116") (name "unconnected-(U11-GPIO12-Pad6)") (class "Default")
      (node (ref "U11") (pin "6") (pinfunction "GPIO12_6") (pintype "bidirectional"))
    )
    (net (code "117") (name "unconnected-(U11-GPIO13-Pad7)") (class "Default")
      (node (ref "U11") (pin "7") (pinfunction "GPIO13_7") (pintype "bidirectional"))
    )
    (net (code "118") (name "unconnected-(U11-GPIO14-Pad5)") (class "Default")
      (node (ref "U11") (pin "5") (pinfunction "GPIO14_5") (pintype "bidirectional"))
    )
    (net (code "119") (name "unconnected-(U11-GPIO16-Pad4)") (class "Default")
      (node (ref "U11") (pin "4") (pinfunction "GPIO16_4") (pintype "bidirectional"))
    )
  )
)
